# ADC_Board.net
KiCad netlist of a schematic drawn in EAGLE
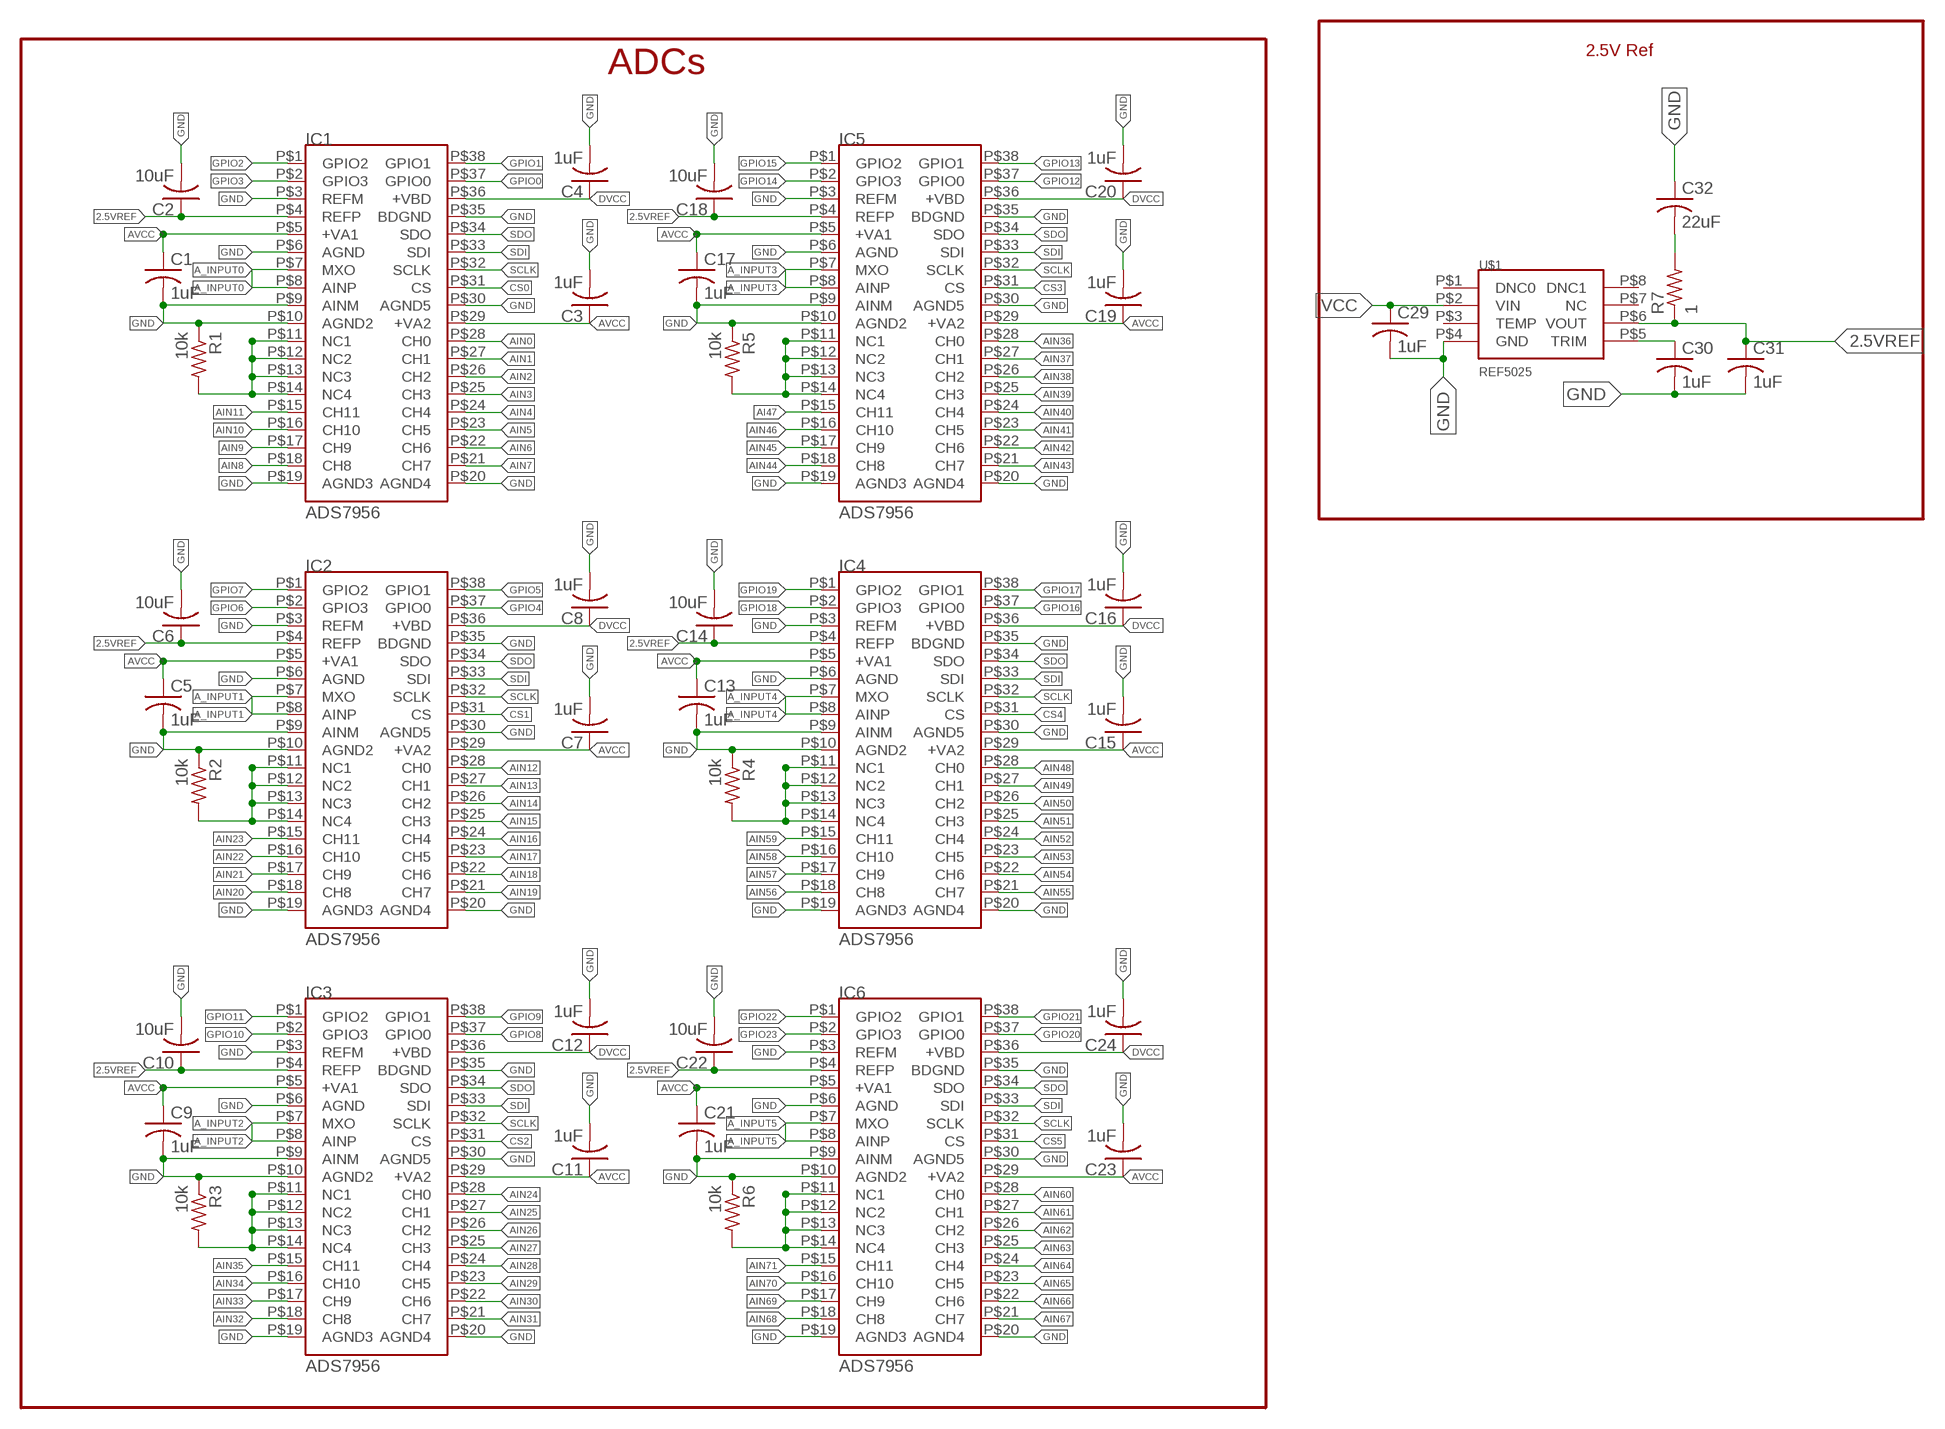
[diagram p0: schematic, sheet 1]

(export (version "E")
  (design (tool "Eeschema 10.0.6"))
  (components
    (comp (ref "C1")
      (value "1uF")
      (footprint "eagle-import:C0603")
      (libsource (lib "eagle-import") (part "C-USC0603"))
    )
    (comp (ref "C2")
      (value "10uF")
      (footprint "eagle-import:C0603")
      (libsource (lib "eagle-import") (part "C-USC0603"))
    )
    (comp (ref "C3")
      (value "1uF")
      (footprint "eagle-import:C0603")
      (libsource (lib "eagle-import") (part "C-USC0603"))
    )
    (comp (ref "C4")
      (value "1uF")
      (footprint "eagle-import:C0603")
      (libsource (lib "eagle-import") (part "C-USC0603"))
    )
    (comp (ref "C5")
      (value "1uF")
      (footprint "eagle-import:C0603")
      (libsource (lib "eagle-import") (part "C-USC0603"))
    )
    (comp (ref "C6")
      (value "10uF")
      (footprint "eagle-import:C0603")
      (libsource (lib "eagle-import") (part "C-USC0603"))
    )
    (comp (ref "C7")
      (value "1uF")
      (footprint "eagle-import:C0603")
      (libsource (lib "eagle-import") (part "C-USC0603"))
    )
    (comp (ref "C8")
      (value "1uF")
      (footprint "eagle-import:C0603")
      (libsource (lib "eagle-import") (part "C-USC0603"))
    )
    (comp (ref "C9")
      (value "1uF")
      (footprint "eagle-import:C0603")
      (libsource (lib "eagle-import") (part "C-USC0603"))
    )
    (comp (ref "C10")
      (value "10uF")
      (footprint "eagle-import:C0603")
      (libsource (lib "eagle-import") (part "C-USC0603"))
    )
    (comp (ref "C11")
      (value "1uF")
      (footprint "eagle-import:C0603")
      (libsource (lib "eagle-import") (part "C-USC0603"))
    )
    (comp (ref "C12")
      (value "1uF")
      (footprint "eagle-import:C0603")
      (libsource (lib "eagle-import") (part "C-USC0603"))
    )
    (comp (ref "C13")
      (value "1uF")
      (footprint "eagle-import:C0603")
      (libsource (lib "eagle-import") (part "C-USC0603"))
    )
    (comp (ref "C14")
      (value "10uF")
      (footprint "eagle-import:C0603")
      (libsource (lib "eagle-import") (part "C-USC0603"))
    )
    (comp (ref "C15")
      (value "1uF")
      (footprint "eagle-import:C0603")
      (libsource (lib "eagle-import") (part "C-USC0603"))
    )
    (comp (ref "C16")
      (value "1uF")
      (footprint "eagle-import:C0603")
      (libsource (lib "eagle-import") (part "C-USC0603"))
    )
    (comp (ref "C17")
      (value "1uF")
      (footprint "eagle-import:C0603")
      (libsource (lib "eagle-import") (part "C-USC0603"))
    )
    (comp (ref "C18")
      (value "10uF")
      (footprint "eagle-import:C0603")
      (libsource (lib "eagle-import") (part "C-USC0603"))
    )
    (comp (ref "C19")
      (value "1uF")
      (footprint "eagle-import:C0603")
      (libsource (lib "eagle-import") (part "C-USC0603"))
    )
    (comp (ref "C20")
      (value "1uF")
      (footprint "eagle-import:C0603")
      (libsource (lib "eagle-import") (part "C-USC0603"))
    )
    (comp (ref "C21")
      (value "1uF")
      (footprint "eagle-import:C0603")
      (libsource (lib "eagle-import") (part "C-USC0603"))
    )
    (comp (ref "C22")
      (value "10uF")
      (footprint "eagle-import:C0603")
      (libsource (lib "eagle-import") (part "C-USC0603"))
    )
    (comp (ref "C23")
      (value "1uF")
      (footprint "eagle-import:C0603")
      (libsource (lib "eagle-import") (part "C-USC0603"))
    )
    (comp (ref "C24")
      (value "1uF")
      (footprint "eagle-import:C0603")
      (libsource (lib "eagle-import") (part "C-USC0603"))
    )
    (comp (ref "C29")
      (value "1uF")
      (footprint "eagle-import:C0603")
      (libsource (lib "eagle-import") (part "C-USC0603"))
    )
    (comp (ref "C30")
      (value "1uF")
      (footprint "eagle-import:C0603")
      (libsource (lib "eagle-import") (part "C-USC0603"))
    )
    (comp (ref "C31")
      (value "1uF")
      (footprint "eagle-import:C0603")
      (libsource (lib "eagle-import") (part "C-USC0603"))
    )
    (comp (ref "C32")
      (value "22uF")
      (footprint "eagle-import:C0603")
      (libsource (lib "eagle-import") (part "C-USC0603"))
    )
    (comp (ref "IC1")
      (value "ADS7956")
      (footprint "eagle-import:TSSOP-38")
      (libsource (lib "eagle-import") (part "ADS7956"))
    )
    (comp (ref "IC2")
      (value "ADS7956")
      (footprint "eagle-import:TSSOP-38")
      (libsource (lib "eagle-import") (part "ADS7956"))
    )
    (comp (ref "IC3")
      (value "ADS7956")
      (footprint "eagle-import:TSSOP-38")
      (libsource (lib "eagle-import") (part "ADS7956"))
    )
    (comp (ref "IC4")
      (value "ADS7956")
      (footprint "eagle-import:TSSOP-38")
      (libsource (lib "eagle-import") (part "ADS7956"))
    )
    (comp (ref "IC5")
      (value "ADS7956")
      (footprint "eagle-import:TSSOP-38")
      (libsource (lib "eagle-import") (part "ADS7956"))
    )
    (comp (ref "IC6")
      (value "ADS7956")
      (footprint "eagle-import:TSSOP-38")
      (libsource (lib "eagle-import") (part "ADS7956"))
    )
    (comp (ref "R1")
      (value "10k")
      (footprint "eagle-import:R0603")
      (libsource (lib "eagle-import") (part "resistor_R-US_R0603"))
    )
    (comp (ref "R2")
      (value "10k")
      (footprint "eagle-import:R0603")
      (libsource (lib "eagle-import") (part "resistor_R-US_R0603"))
    )
    (comp (ref "R3")
      (value "10k")
      (footprint "eagle-import:R0603")
      (libsource (lib "eagle-import") (part "resistor_R-US_R0603"))
    )
    (comp (ref "R4")
      (value "10k")
      (footprint "eagle-import:R0603")
      (libsource (lib "eagle-import") (part "resistor_R-US_R0603"))
    )
    (comp (ref "R5")
      (value "10k")
      (footprint "eagle-import:R0603")
      (libsource (lib "eagle-import") (part "resistor_R-US_R0603"))
    )
    (comp (ref "R6")
      (value "10k")
      (footprint "eagle-import:R0603")
      (libsource (lib "eagle-import") (part "resistor_R-US_R0603"))
    )
    (comp (ref "R7")
      (value "1")
      (footprint "eagle-import:M0805")
      (libsource (lib "eagle-import") (part "R-US_M0805"))
    )
    (comp (ref "U$1")
      (value "REF5025")
      (footprint "eagle-import:TSSOP-8(TI)")
      (libsource (lib "eagle-import") (part "REF5025"))
    )
  )
  (nets
    (net (code "1") (name "2.5VREF") (class "Default")
      (node (ref "C10") (pin "1") (pinfunction "1_1") (pintype "passive"))
      (node (ref "C14") (pin "1") (pinfunction "1_1") (pintype "passive"))
      (node (ref "C18") (pin "1") (pinfunction "1_1") (pintype "passive"))
      (node (ref "C2") (pin "1") (pinfunction "1_1") (pintype "passive"))
      (node (ref "C22") (pin "1") (pinfunction "1_1") (pintype "passive"))
      (node (ref "C31") (pin "1") (pinfunction "1_1") (pintype "passive"))
      (node (ref "C6") (pin "1") (pinfunction "1_1") (pintype "passive"))
      (node (ref "IC1") (pin "P$4") (pinfunction "REFP_P$4") (pintype "bidirectional"))
      (node (ref "IC2") (pin "P$4") (pinfunction "REFP_P$4") (pintype "bidirectional"))
      (node (ref "IC3") (pin "P$4") (pinfunction "REFP_P$4") (pintype "bidirectional"))
      (node (ref "IC4") (pin "P$4") (pinfunction "REFP_P$4") (pintype "bidirectional"))
      (node (ref "IC5") (pin "P$4") (pinfunction "REFP_P$4") (pintype "bidirectional"))
      (node (ref "IC6") (pin "P$4") (pinfunction "REFP_P$4") (pintype "bidirectional"))
      (node (ref "R7") (pin "1") (pinfunction "1_1") (pintype "passive"))
      (node (ref "U$1") (pin "P$6") (pinfunction "VOUT_P$6") (pintype "bidirectional"))
    )
    (net (code "2") (name "AI47") (class "Default")
      (node (ref "IC5") (pin "P$15") (pinfunction "CH11_P$15") (pintype "bidirectional"))
    )
    (net (code "3") (name "AIN0") (class "Default")
      (node (ref "IC1") (pin "P$28") (pinfunction "CH0_P$28") (pintype "bidirectional"))
    )
    (net (code "4") (name "AIN1") (class "Default")
      (node (ref "IC1") (pin "P$27") (pinfunction "CH1_P$27") (pintype "bidirectional"))
    )
    (net (code "5") (name "AIN2") (class "Default")
      (node (ref "IC1") (pin "P$26") (pinfunction "CH2_P$26") (pintype "bidirectional"))
    )
    (net (code "6") (name "AIN3") (class "Default")
      (node (ref "IC1") (pin "P$25") (pinfunction "CH3_P$25") (pintype "bidirectional"))
    )
    (net (code "7") (name "AIN4") (class "Default")
      (node (ref "IC1") (pin "P$24") (pinfunction "CH4_P$24") (pintype "bidirectional"))
    )
    (net (code "8") (name "AIN5") (class "Default")
      (node (ref "IC1") (pin "P$23") (pinfunction "CH5_P$23") (pintype "bidirectional"))
    )
    (net (code "9") (name "AIN6") (class "Default")
      (node (ref "IC1") (pin "P$22") (pinfunction "CH6_P$22") (pintype "bidirectional"))
    )
    (net (code "10") (name "AIN7") (class "Default")
      (node (ref "IC1") (pin "P$21") (pinfunction "CH7_P$21") (pintype "bidirectional"))
    )
    (net (code "11") (name "AIN8") (class "Default")
      (node (ref "IC1") (pin "P$18") (pinfunction "CH8_P$18") (pintype "bidirectional"))
    )
    (net (code "12") (name "AIN9") (class "Default")
      (node (ref "IC1") (pin "P$17") (pinfunction "CH9_P$17") (pintype "bidirectional"))
    )
    (net (code "13") (name "AIN10") (class "Default")
      (node (ref "IC1") (pin "P$16") (pinfunction "CH10_P$16") (pintype "bidirectional"))
    )
    (net (code "14") (name "AIN11") (class "Default")
      (node (ref "IC1") (pin "P$15") (pinfunction "CH11_P$15") (pintype "bidirectional"))
    )
    (net (code "15") (name "AIN12") (class "Default")
      (node (ref "IC2") (pin "P$28") (pinfunction "CH0_P$28") (pintype "bidirectional"))
    )
    (net (code "16") (name "AIN13") (class "Default")
      (node (ref "IC2") (pin "P$27") (pinfunction "CH1_P$27") (pintype "bidirectional"))
    )
    (net (code "17") (name "AIN14") (class "Default")
      (node (ref "IC2") (pin "P$26") (pinfunction "CH2_P$26") (pintype "bidirectional"))
    )
    (net (code "18") (name "AIN15") (class "Default")
      (node (ref "IC2") (pin "P$25") (pinfunction "CH3_P$25") (pintype "bidirectional"))
    )
    (net (code "19") (name "AIN16") (class "Default")
      (node (ref "IC2") (pin "P$24") (pinfunction "CH4_P$24") (pintype "bidirectional"))
    )
    (net (code "20") (name "AIN17") (class "Default")
      (node (ref "IC2") (pin "P$23") (pinfunction "CH5_P$23") (pintype "bidirectional"))
    )
    (net (code "21") (name "AIN18") (class "Default")
      (node (ref "IC2") (pin "P$22") (pinfunction "CH6_P$22") (pintype "bidirectional"))
    )
    (net (code "22") (name "AIN19") (class "Default")
      (node (ref "IC2") (pin "P$21") (pinfunction "CH7_P$21") (pintype "bidirectional"))
    )
    (net (code "23") (name "AIN20") (class "Default")
      (node (ref "IC2") (pin "P$18") (pinfunction "CH8_P$18") (pintype "bidirectional"))
    )
    (net (code "24") (name "AIN21") (class "Default")
      (node (ref "IC2") (pin "P$17") (pinfunction "CH9_P$17") (pintype "bidirectional"))
    )
    (net (code "25") (name "AIN22") (class "Default")
      (node (ref "IC2") (pin "P$16") (pinfunction "CH10_P$16") (pintype "bidirectional"))
    )
    (net (code "26") (name "AIN23") (class "Default")
      (node (ref "IC2") (pin "P$15") (pinfunction "CH11_P$15") (pintype "bidirectional"))
    )
    (net (code "27") (name "AIN24") (class "Default")
      (node (ref "IC3") (pin "P$28") (pinfunction "CH0_P$28") (pintype "bidirectional"))
    )
    (net (code "28") (name "AIN25") (class "Default")
      (node (ref "IC3") (pin "P$27") (pinfunction "CH1_P$27") (pintype "bidirectional"))
    )
    (net (code "29") (name "AIN26") (class "Default")
      (node (ref "IC3") (pin "P$26") (pinfunction "CH2_P$26") (pintype "bidirectional"))
    )
    (net (code "30") (name "AIN27") (class "Default")
      (node (ref "IC3") (pin "P$25") (pinfunction "CH3_P$25") (pintype "bidirectional"))
    )
    (net (code "31") (name "AIN28") (class "Default")
      (node (ref "IC3") (pin "P$24") (pinfunction "CH4_P$24") (pintype "bidirectional"))
    )
    (net (code "32") (name "AIN29") (class "Default")
      (node (ref "IC3") (pin "P$23") (pinfunction "CH5_P$23") (pintype "bidirectional"))
    )
    (net (code "33") (name "AIN30") (class "Default")
      (node (ref "IC3") (pin "P$22") (pinfunction "CH6_P$22") (pintype "bidirectional"))
    )
    (net (code "34") (name "AIN31") (class "Default")
      (node (ref "IC3") (pin "P$21") (pinfunction "CH7_P$21") (pintype "bidirectional"))
    )
    (net (code "35") (name "AIN32") (class "Default")
      (node (ref "IC3") (pin "P$18") (pinfunction "CH8_P$18") (pintype "bidirectional"))
    )
    (net (code "36") (name "AIN33") (class "Default")
      (node (ref "IC3") (pin "P$17") (pinfunction "CH9_P$17") (pintype "bidirectional"))
    )
    (net (code "37") (name "AIN34") (class "Default")
      (node (ref "IC3") (pin "P$16") (pinfunction "CH10_P$16") (pintype "bidirectional"))
    )
    (net (code "38") (name "AIN35") (class "Default")
      (node (ref "IC3") (pin "P$15") (pinfunction "CH11_P$15") (pintype "bidirectional"))
    )
    (net (code "39") (name "AIN36") (class "Default")
      (node (ref "IC5") (pin "P$28") (pinfunction "CH0_P$28") (pintype "bidirectional"))
    )
    (net (code "40") (name "AIN37") (class "Default")
      (node (ref "IC5") (pin "P$27") (pinfunction "CH1_P$27") (pintype "bidirectional"))
    )
    (net (code "41") (name "AIN38") (class "Default")
      (node (ref "IC5") (pin "P$26") (pinfunction "CH2_P$26") (pintype "bidirectional"))
    )
    (net (code "42") (name "AIN39") (class "Default")
      (node (ref "IC5") (pin "P$25") (pinfunction "CH3_P$25") (pintype "bidirectional"))
    )
    (net (code "43") (name "AIN40") (class "Default")
      (node (ref "IC5") (pin "P$24") (pinfunction "CH4_P$24") (pintype "bidirectional"))
    )
    (net (code "44") (name "AIN41") (class "Default")
      (node (ref "IC5") (pin "P$23") (pinfunction "CH5_P$23") (pintype "bidirectional"))
    )
    (net (code "45") (name "AIN42") (class "Default")
      (node (ref "IC5") (pin "P$22") (pinfunction "CH6_P$22") (pintype "bidirectional"))
    )
    (net (code "46") (name "AIN43") (class "Default")
      (node (ref "IC5") (pin "P$21") (pinfunction "CH7_P$21") (pintype "bidirectional"))
    )
    (net (code "47") (name "AIN44") (class "Default")
      (node (ref "IC5") (pin "P$18") (pinfunction "CH8_P$18") (pintype "bidirectional"))
    )
    (net (code "48") (name "AIN45") (class "Default")
      (node (ref "IC5") (pin "P$17") (pinfunction "CH9_P$17") (pintype "bidirectional"))
    )
    (net (code "49") (name "AIN46") (class "Default")
      (node (ref "IC5") (pin "P$16") (pinfunction "CH10_P$16") (pintype "bidirectional"))
    )
    (net (code "50") (name "AIN48") (class "Default")
      (node (ref "IC4") (pin "P$28") (pinfunction "CH0_P$28") (pintype "bidirectional"))
    )
    (net (code "51") (name "AIN49") (class "Default")
      (node (ref "IC4") (pin "P$27") (pinfunction "CH1_P$27") (pintype "bidirectional"))
    )
    (net (code "52") (name "AIN50") (class "Default")
      (node (ref "IC4") (pin "P$26") (pinfunction "CH2_P$26") (pintype "bidirectional"))
    )
    (net (code "53") (name "AIN51") (class "Default")
      (node (ref "IC4") (pin "P$25") (pinfunction "CH3_P$25") (pintype "bidirectional"))
    )
    (net (code "54") (name "AIN52") (class "Default")
      (node (ref "IC4") (pin "P$24") (pinfunction "CH4_P$24") (pintype "bidirectional"))
    )
    (net (code "55") (name "AIN53") (class "Default")
      (node (ref "IC4") (pin "P$23") (pinfunction "CH5_P$23") (pintype "bidirectional"))
    )
    (net (code "56") (name "AIN54") (class "Default")
      (node (ref "IC4") (pin "P$22") (pinfunction "CH6_P$22") (pintype "bidirectional"))
    )
    (net (code "57") (name "AIN55") (class "Default")
      (node (ref "IC4") (pin "P$21") (pinfunction "CH7_P$21") (pintype "bidirectional"))
    )
    (net (code "58") (name "AIN56") (class "Default")
      (node (ref "IC4") (pin "P$18") (pinfunction "CH8_P$18") (pintype "bidirectional"))
    )
    (net (code "59") (name "AIN57") (class "Default")
      (node (ref "IC4") (pin "P$17") (pinfunction "CH9_P$17") (pintype "bidirectional"))
    )
    (net (code "60") (name "AIN58") (class "Default")
      (node (ref "IC4") (pin "P$16") (pinfunction "CH10_P$16") (pintype "bidirectional"))
    )
    (net (code "61") (name "AIN59") (class "Default")
      (node (ref "IC4") (pin "P$15") (pinfunction "CH11_P$15") (pintype "bidirectional"))
    )
    (net (code "62") (name "AIN60") (class "Default")
      (node (ref "IC6") (pin "P$28") (pinfunction "CH0_P$28") (pintype "bidirectional"))
    )
    (net (code "63") (name "AIN61") (class "Default")
      (node (ref "IC6") (pin "P$27") (pinfunction "CH1_P$27") (pintype "bidirectional"))
    )
    (net (code "64") (name "AIN62") (class "Default")
      (node (ref "IC6") (pin "P$26") (pinfunction "CH2_P$26") (pintype "bidirectional"))
    )
    (net (code "65") (name "AIN63") (class "Default")
      (node (ref "IC6") (pin "P$25") (pinfunction "CH3_P$25") (pintype "bidirectional"))
    )
    (net (code "66") (name "AIN64") (class "Default")
      (node (ref "IC6") (pin "P$24") (pinfunction "CH4_P$24") (pintype "bidirectional"))
    )
    (net (code "67") (name "AIN65") (class "Default")
      (node (ref "IC6") (pin "P$23") (pinfunction "CH5_P$23") (pintype "bidirectional"))
    )
    (net (code "68") (name "AIN66") (class "Default")
      (node (ref "IC6") (pin "P$22") (pinfunction "CH6_P$22") (pintype "bidirectional"))
    )
    (net (code "69") (name "AIN67") (class "Default")
      (node (ref "IC6") (pin "P$21") (pinfunction "CH7_P$21") (pintype "bidirectional"))
    )
    (net (code "70") (name "AIN68") (class "Default")
      (node (ref "IC6") (pin "P$18") (pinfunction "CH8_P$18") (pintype "bidirectional"))
    )
    (net (code "71") (name "AIN69") (class "Default")
      (node (ref "IC6") (pin "P$17") (pinfunction "CH9_P$17") (pintype "bidirectional"))
    )
    (net (code "72") (name "AIN70") (class "Default")
      (node (ref "IC6") (pin "P$16") (pinfunction "CH10_P$16") (pintype "bidirectional"))
    )
    (net (code "73") (name "AIN71") (class "Default")
      (node (ref "IC6") (pin "P$15") (pinfunction "CH11_P$15") (pintype "bidirectional"))
    )
    (net (code "74") (name "AVCC") (class "Default")
      (node (ref "C1") (pin "1") (pinfunction "1_1") (pintype "passive"))
      (node (ref "C11") (pin "1") (pinfunction "1_1") (pintype "passive"))
      (node (ref "C13") (pin "1") (pinfunction "1_1") (pintype "passive"))
      (node (ref "C15") (pin "1") (pinfunction "1_1") (pintype "passive"))
      (node (ref "C17") (pin "1") (pinfunction "1_1") (pintype "passive"))
      (node (ref "C19") (pin "1") (pinfunction "1_1") (pintype "passive"))
      (node (ref "C21") (pin "1") (pinfunction "1_1") (pintype "passive"))
      (node (ref "C23") (pin "1") (pinfunction "1_1") (pintype "passive"))
      (node (ref "C3") (pin "1") (pinfunction "1_1") (pintype "passive"))
      (node (ref "C5") (pin "1") (pinfunction "1_1") (pintype "passive"))
      (node (ref "C7") (pin "1") (pinfunction "1_1") (pintype "passive"))
      (node (ref "C9") (pin "1") (pinfunction "1_1") (pintype "passive"))
      (node (ref "IC1") (pin "P$29") (pinfunction "+VA2_P$29") (pintype "bidirectional"))
      (node (ref "IC1") (pin "P$5") (pinfunction "+VA1_P$5") (pintype "bidirectional"))
      (node (ref "IC2") (pin "P$29") (pinfunction "+VA2_P$29") (pintype "bidirectional"))
      (node (ref "IC2") (pin "P$5") (pinfunction "+VA1_P$5") (pintype "bidirectional"))
      (node (ref "IC3") (pin "P$29") (pinfunction "+VA2_P$29") (pintype "bidirectional"))
      (node (ref "IC3") (pin "P$5") (pinfunction "+VA1_P$5") (pintype "bidirectional"))
      (node (ref "IC4") (pin "P$29") (pinfunction "+VA2_P$29") (pintype "bidirectional"))
      (node (ref "IC4") (pin "P$5") (pinfunction "+VA1_P$5") (pintype "bidirectional"))
      (node (ref "IC5") (pin "P$29") (pinfunction "+VA2_P$29") (pintype "bidirectional"))
      (node (ref "IC5") (pin "P$5") (pinfunction "+VA1_P$5") (pintype "bidirectional"))
      (node (ref "IC6") (pin "P$29") (pinfunction "+VA2_P$29") (pintype "bidirectional"))
      (node (ref "IC6") (pin "P$5") (pinfunction "+VA1_P$5") (pintype "bidirectional"))
    )
    (net (code "75") (name "A_INPUT0") (class "Default")
      (node (ref "IC1") (pin "P$7") (pinfunction "MXO_P$7") (pintype "bidirectional"))
      (node (ref "IC1") (pin "P$8") (pinfunction "AINP_P$8") (pintype "bidirectional"))
    )
    (net (code "76") (name "A_INPUT1") (class "Default")
      (node (ref "IC2") (pin "P$7") (pinfunction "MXO_P$7") (pintype "bidirectional"))
      (node (ref "IC2") (pin "P$8") (pinfunction "AINP_P$8") (pintype "bidirectional"))
    )
    (net (code "77") (name "A_INPUT2") (class "Default")
      (node (ref "IC3") (pin "P$7") (pinfunction "MXO_P$7") (pintype "bidirectional"))
      (node (ref "IC3") (pin "P$8") (pinfunction "AINP_P$8") (pintype "bidirectional"))
    )
    (net (code "78") (name "A_INPUT3") (class "Default")
      (node (ref "IC5") (pin "P$7") (pinfunction "MXO_P$7") (pintype "bidirectional"))
      (node (ref "IC5") (pin "P$8") (pinfunction "AINP_P$8") (pintype "bidirectional"))
    )
    (net (code "79") (name "A_INPUT4") (class "Default")
      (node (ref "IC4") (pin "P$7") (pinfunction "MXO_P$7") (pintype "bidirectional"))
      (node (ref "IC4") (pin "P$8") (pinfunction "AINP_P$8") (pintype "bidirectional"))
    )
    (net (code "80") (name "A_INPUT5") (class "Default")
      (node (ref "IC6") (pin "P$7") (pinfunction "MXO_P$7") (pintype "bidirectional"))
      (node (ref "IC6") (pin "P$8") (pinfunction "AINP_P$8") (pintype "bidirectional"))
    )
    (net (code "81") (name "CS0") (class "Default")
      (node (ref "IC1") (pin "P$31") (pinfunction "CS_P$31") (pintype "bidirectional"))
    )
    (net (code "82") (name "CS1") (class "Default")
      (node (ref "IC2") (pin "P$31") (pinfunction "CS_P$31") (pintype "bidirectional"))
    )
    (net (code "83") (name "CS2") (class "Default")
      (node (ref "IC3") (pin "P$31") (pinfunction "CS_P$31") (pintype "bidirectional"))
    )
    (net (code "84") (name "CS3") (class "Default")
      (node (ref "IC5") (pin "P$31") (pinfunction "CS_P$31") (pintype "bidirectional"))
    )
    (net (code "85") (name "CS4") (class "Default")
      (node (ref "IC4") (pin "P$31") (pinfunction "CS_P$31") (pintype "bidirectional"))
    )
    (net (code "86") (name "CS5") (class "Default")
      (node (ref "IC6") (pin "P$31") (pinfunction "CS_P$31") (pintype "bidirectional"))
    )
    (net (code "87") (name "DVCC") (class "Default")
      (node (ref "C12") (pin "1") (pinfunction "1_1") (pintype "passive"))
      (node (ref "C16") (pin "1") (pinfunction "1_1") (pintype "passive"))
      (node (ref "C20") (pin "1") (pinfunction "1_1") (pintype "passive"))
      (node (ref "C24") (pin "1") (pinfunction "1_1") (pintype "passive"))
      (node (ref "C4") (pin "1") (pinfunction "1_1") (pintype "passive"))
      (node (ref "C8") (pin "1") (pinfunction "1_1") (pintype "passive"))
      (node (ref "IC1") (pin "P$36") (pinfunction "+VBD_P$36") (pintype "bidirectional"))
      (node (ref "IC2") (pin "P$36") (pinfunction "+VBD_P$36") (pintype "bidirectional"))
      (node (ref "IC3") (pin "P$36") (pinfunction "+VBD_P$36") (pintype "bidirectional"))
      (node (ref "IC4") (pin "P$36") (pinfunction "+VBD_P$36") (pintype "bidirectional"))
      (node (ref "IC5") (pin "P$36") (pinfunction "+VBD_P$36") (pintype "bidirectional"))
      (node (ref "IC6") (pin "P$36") (pinfunction "+VBD_P$36") (pintype "bidirectional"))
    )
    (net (code "88") (name "GND") (class "Default")
      (node (ref "C1") (pin "2") (pinfunction "2_2") (pintype "passive"))
      (node (ref "C10") (pin "2") (pinfunction "2_2") (pintype "passive"))
      (node (ref "C11") (pin "2") (pinfunction "2_2") (pintype "passive"))
      (node (ref "C12") (pin "2") (pinfunction "2_2") (pintype "passive"))
      (node (ref "C13") (pin "2") (pinfunction "2_2") (pintype "passive"))
      (node (ref "C14") (pin "2") (pinfunction "2_2") (pintype "passive"))
      (node (ref "C15") (pin "2") (pinfunction "2_2") (pintype "passive"))
      (node (ref "C16") (pin "2") (pinfunction "2_2") (pintype "passive"))
      (node (ref "C17") (pin "2") (pinfunction "2_2") (pintype "passive"))
      (node (ref "C18") (pin "2") (pinfunction "2_2") (pintype "passive"))
      (node (ref "C19") (pin "2") (pinfunction "2_2") (pintype "passive"))
      (node (ref "C2") (pin "2") (pinfunction "2_2") (pintype "passive"))
      (node (ref "C20") (pin "2") (pinfunction "2_2") (pintype "passive"))
      (node (ref "C21") (pin "2") (pinfunction "2_2") (pintype "passive"))
      (node (ref "C22") (pin "2") (pinfunction "2_2") (pintype "passive"))
      (node (ref "C23") (pin "2") (pinfunction "2_2") (pintype "passive"))
      (node (ref "C24") (pin "2") (pinfunction "2_2") (pintype "passive"))
      (node (ref "C29") (pin "2") (pinfunction "2_2") (pintype "passive"))
      (node (ref "C3") (pin "2") (pinfunction "2_2") (pintype "passive"))
      (node (ref "C30") (pin "2") (pinfunction "2_2") (pintype "passive"))
      (node (ref "C31") (pin "2") (pinfunction "2_2") (pintype "passive"))
      (node (ref "C32") (pin "1") (pinfunction "1_1") (pintype "passive"))
      (node (ref "C4") (pin "2") (pinfunction "2_2") (pintype "passive"))
      (node (ref "C5") (pin "2") (pinfunction "2_2") (pintype "passive"))
      (node (ref "C6") (pin "2") (pinfunction "2_2") (pintype "passive"))
      (node (ref "C7") (pin "2") (pinfunction "2_2") (pintype "passive"))
      (node (ref "C8") (pin "2") (pinfunction "2_2") (pintype "passive"))
      (node (ref "C9") (pin "2") (pinfunction "2_2") (pintype "passive"))
      (node (ref "IC1") (pin "P$10") (pinfunction "AGND2_P$10") (pintype "bidirectional"))
      (node (ref "IC1") (pin "P$19") (pinfunction "AGND3_P$19") (pintype "bidirectional"))
      (node (ref "IC1") (pin "P$20") (pinfunction "AGND4_P$20") (pintype "bidirectional"))
      (node (ref "IC1") (pin "P$3") (pinfunction "REFM_P$3") (pintype "bidirectional"))
      (node (ref "IC1") (pin "P$30") (pinfunction "AGND5_P$30") (pintype "bidirectional"))
      (node (ref "IC1") (pin "P$35") (pinfunction "BDGND_P$35") (pintype "bidirectional"))
      (node (ref "IC1") (pin "P$6") (pinfunction "AGND_P$6") (pintype "bidirectional"))
      (node (ref "IC1") (pin "P$9") (pinfunction "AINM_P$9") (pintype "bidirectional"))
      (node (ref "IC2") (pin "P$10") (pinfunction "AGND2_P$10") (pintype "bidirectional"))
      (node (ref "IC2") (pin "P$19") (pinfunction "AGND3_P$19") (pintype "bidirectional"))
      (node (ref "IC2") (pin "P$20") (pinfunction "AGND4_P$20") (pintype "bidirectional"))
      (node (ref "IC2") (pin "P$3") (pinfunction "REFM_P$3") (pintype "bidirectional"))
      (node (ref "IC2") (pin "P$30") (pinfunction "AGND5_P$30") (pintype "bidirectional"))
      (node (ref "IC2") (pin "P$35") (pinfunction "BDGND_P$35") (pintype "bidirectional"))
      (node (ref "IC2") (pin "P$6") (pinfunction "AGND_P$6") (pintype "bidirectional"))
      (node (ref "IC2") (pin "P$9") (pinfunction "AINM_P$9") (pintype "bidirectional"))
      (node (ref "IC3") (pin "P$10") (pinfunction "AGND2_P$10") (pintype "bidirectional"))
      (node (ref "IC3") (pin "P$19") (pinfunction "AGND3_P$19") (pintype "bidirectional"))
      (node (ref "IC3") (pin "P$20") (pinfunction "AGND4_P$20") (pintype "bidirectional"))
      (node (ref "IC3") (pin "P$3") (pinfunction "REFM_P$3") (pintype "bidirectional"))
      (node (ref "IC3") (pin "P$30") (pinfunction "AGND5_P$30") (pintype "bidirectional"))
      (node (ref "IC3") (pin "P$35") (pinfunction "BDGND_P$35") (pintype "bidirectional"))
      (node (ref "IC3") (pin "P$6") (pinfunction "AGND_P$6") (pintype "bidirectional"))
      (node (ref "IC3") (pin "P$9") (pinfunction "AINM_P$9") (pintype "bidirectional"))
      (node (ref "IC4") (pin "P$10") (pinfunction "AGND2_P$10") (pintype "bidirectional"))
      (node (ref "IC4") (pin "P$19") (pinfunction "AGND3_P$19") (pintype "bidirectional"))
      (node (ref "IC4") (pin "P$20") (pinfunction "AGND4_P$20") (pintype "bidirectional"))
      (node (ref "IC4") (pin "P$3") (pinfunction "REFM_P$3") (pintype "bidirectional"))
      (node (ref "IC4") (pin "P$30") (pinfunction "AGND5_P$30") (pintype "bidirectional"))
      (node (ref "IC4") (pin "P$35") (pinfunction "BDGND_P$35") (pintype "bidirectional"))
      (node (ref "IC4") (pin "P$6") (pinfunction "AGND_P$6") (pintype "bidirectional"))
      (node (ref "IC4") (pin "P$9") (pinfunction "AINM_P$9") (pintype "bidirectional"))
      (node (ref "IC5") (pin "P$10") (pinfunction "AGND2_P$10") (pintype "bidirectional"))
      (node (ref "IC5") (pin "P$19") (pinfunction "AGND3_P$19") (pintype "bidirectional"))
      (node (ref "IC5") (pin "P$20") (pinfunction "AGND4_P$20") (pintype "bidirectional"))
      (node (ref "IC5") (pin "P$3") (pinfunction "REFM_P$3") (pintype "bidirectional"))
      (node (ref "IC5") (pin "P$30") (pinfunction "AGND5_P$30") (pintype "bidirectional"))
      (node (ref "IC5") (pin "P$35") (pinfunction "BDGND_P$35") (pintype "bidirectional"))
      (node (ref "IC5") (pin "P$6") (pinfunction "AGND_P$6") (pintype "bidirectional"))
      (node (ref "IC5") (pin "P$9") (pinfunction "AINM_P$9") (pintype "bidirectional"))
      (node (ref "IC6") (pin "P$10") (pinfunction "AGND2_P$10") (pintype "bidirectional"))
      (node (ref "IC6") (pin "P$19") (pinfunction "AGND3_P$19") (pintype "bidirectional"))
      (node (ref "IC6") (pin "P$20") (pinfunction "AGND4_P$20") (pintype "bidirectional"))
      (node (ref "IC6") (pin "P$3") (pinfunction "REFM_P$3") (pintype "bidirectional"))
      (node (ref "IC6") (pin "P$30") (pinfunction "AGND5_P$30") (pintype "bidirectional"))
      (node (ref "IC6") (pin "P$35") (pinfunction "BDGND_P$35") (pintype "bidirectional"))
      (node (ref "IC6") (pin "P$6") (pinfunction "AGND_P$6") (pintype "bidirectional"))
      (node (ref "IC6") (pin "P$9") (pinfunction "AINM_P$9") (pintype "bidirectional"))
      (node (ref "R1") (pin "1") (pinfunction "1_1") (pintype "passive"))
      (node (ref "R2") (pin "1") (pinfunction "1_1") (pintype "passive"))
      (node (ref "R3") (pin "1") (pinfunction "1_1") (pintype "passive"))
      (node (ref "R4") (pin "1") (pinfunction "1_1") (pintype "passive"))
      (node (ref "R5") (pin "1") (pinfunction "1_1") (pintype "passive"))
      (node (ref "R6") (pin "1") (pinfunction "1_1") (pintype "passive"))
      (node (ref "U$1") (pin "P$4") (pinfunction "GND_P$4") (pintype "bidirectional"))
    )
    (net (code "89") (name "GPIO0") (class "Default")
      (node (ref "IC1") (pin "P$37") (pinfunction "GPIO0_P$37") (pintype "bidirectional"))
    )
    (net (code "90") (name "GPIO1") (class "Default")
      (node (ref "IC1") (pin "P$38") (pinfunction "GPIO1_P$38") (pintype "bidirectional"))
    )
    (net (code "91") (name "GPIO2") (class "Default")
      (node (ref "IC1") (pin "P$1") (pinfunction "GPIO2_P$1") (pintype "bidirectional"))
    )
    (net (code "92") (name "GPIO3") (class "Default")
      (node (ref "IC1") (pin "P$2") (pinfunction "GPIO3_P$2") (pintype "bidirectional"))
    )
    (net (code "93") (name "GPIO4") (class "Default")
      (node (ref "IC2") (pin "P$37") (pinfunction "GPIO0_P$37") (pintype "bidirectional"))
    )
    (net (code "94") (name "GPIO5") (class "Default")
      (node (ref "IC2") (pin "P$38") (pinfunction "GPIO1_P$38") (pintype "bidirectional"))
    )
    (net (code "95") (name "GPIO6") (class "Default")
      (node (ref "IC2") (pin "P$2") (pinfunction "GPIO3_P$2") (pintype "bidirectional"))
    )
    (net (code "96") (name "GPIO7") (class "Default")
      (node (ref "IC2") (pin "P$1") (pinfunction "GPIO2_P$1") (pintype "bidirectional"))
    )
    (net (code "97") (name "GPIO8") (class "Default")
      (node (ref "IC3") (pin "P$37") (pinfunction "GPIO0_P$37") (pintype "bidirectional"))
    )
    (net (code "98") (name "GPIO9") (class "Default")
      (node (ref "IC3") (pin "P$38") (pinfunction "GPIO1_P$38") (pintype "bidirectional"))
    )
    (net (code "99") (name "GPIO10") (class "Default")
      (node (ref "IC3") (pin "P$2") (pinfunction "GPIO3_P$2") (pintype "bidirectional"))
    )
    (net (code "100") (name "GPIO11") (class "Default")
      (node (ref "IC3") (pin "P$1") (pinfunction "GPIO2_P$1") (pintype "bidirectional"))
    )
    (net (code "101") (name "GPIO12") (class "Default")
      (node (ref "IC5") (pin "P$37") (pinfunction "GPIO0_P$37") (pintype "bidirectional"))
    )
    (net (code "102") (name "GPIO13") (class "Default")
      (node (ref "IC5") (pin "P$38") (pinfunction "GPIO1_P$38") (pintype "bidirectional"))
    )
    (net (code "103") (name "GPIO14") (class "Default")
      (node (ref "IC5") (pin "P$2") (pinfunction "GPIO3_P$2") (pintype "bidirectional"))
    )
    (net (code "104") (name "GPIO15") (class "Default")
      (node (ref "IC5") (pin "P$1") (pinfunction "GPIO2_P$1") (pintype "bidirectional"))
    )
    (net (code "105") (name "GPIO16") (class "Default")
      (node (ref "IC4") (pin "P$37") (pinfunction "GPIO0_P$37") (pintype "bidirectional"))
    )
    (net (code "106") (name "GPIO17") (class "Default")
      (node (ref "IC4") (pin "P$38") (pinfunction "GPIO1_P$38") (pintype "bidirectional"))
    )
    (net (code "107") (name "GPIO18") (class "Default")
      (node (ref "IC4") (pin "P$2") (pinfunction "GPIO3_P$2") (pintype "bidirectional"))
    )
    (net (code "108") (name "GPIO19") (class "Default")
      (node (ref "IC4") (pin "P$1") (pinfunction "GPIO2_P$1") (pintype "bidirectional"))
    )
    (net (code "109") (name "GPIO20") (class "Default")
      (node (ref "IC6") (pin "P$37") (pinfunction "GPIO0_P$37") (pintype "bidirectional"))
    )
    (net (code "110") (name "GPIO21") (class "Default")
      (node (ref "IC6") (pin "P$38") (pinfunction "GPIO1_P$38") (pintype "bidirectional"))
    )
    (net (code "111") (name "GPIO22") (class "Default")
      (node (ref "IC6") (pin "P$1") (pinfunction "GPIO2_P$1") (pintype "bidirectional"))
    )
    (net (code "112") (name "GPIO23") (class "Default")
      (node (ref "IC6") (pin "P$2") (pinfunction "GPIO3_P$2") (pintype "bidirectional"))
    )
    (net (code "113") (name "Net-(C32-Pad2)") (class "Default")
      (node (ref "C32") (pin "2") (pinfunction "2_2") (pintype "passive"))
      (node (ref "R7") (pin "2") (pinfunction "2_2") (pintype "passive"))
    )
    (net (code "114") (name "Net-(IC1-NC1)") (class "Default")
      (node (ref "IC1") (pin "P$11") (pinfunction "NC1_P$11") (pintype "bidirectional"))
      (node (ref "IC1") (pin "P$12") (pinfunction "NC2_P$12") (pintype "bidirectional"))
      (node (ref "IC1") (pin "P$13") (pinfunction "NC3_P$13") (pintype "bidirectional"))
      (node (ref "IC1") (pin "P$14") (pinfunction "NC4_P$14") (pintype "bidirectional"))
      (node (ref "R1") (pin "2") (pinfunction "2_2") (pintype "passive"))
    )
    (net (code "115") (name "Net-(IC2-NC1)") (class "Default")
      (node (ref "IC2") (pin "P$11") (pinfunction "NC1_P$11") (pintype "bidirectional"))
      (node (ref "IC2") (pin "P$12") (pinfunction "NC2_P$12") (pintype "bidirectional"))
      (node (ref "IC2") (pin "P$13") (pinfunction "NC3_P$13") (pintype "bidirectional"))
      (node (ref "IC2") (pin "P$14") (pinfunction "NC4_P$14") (pintype "bidirectional"))
      (node (ref "R2") (pin "2") (pinfunction "2_2") (pintype "passive"))
    )
    (net (code "116") (name "Net-(IC3-NC1)") (class "Default")
      (node (ref "IC3") (pin "P$11") (pinfunction "NC1_P$11") (pintype "bidirectional"))
      (node (ref "IC3") (pin "P$12") (pinfunction "NC2_P$12") (pintype "bidirectional"))
      (node (ref "IC3") (pin "P$13") (pinfunction "NC3_P$13") (pintype "bidirectional"))
      (node (ref "IC3") (pin "P$14") (pinfunction "NC4_P$14") (pintype "bidirectional"))
      (node (ref "R3") (pin "2") (pinfunction "2_2") (pintype "passive"))
    )
    (net (code "117") (name "Net-(IC4-NC1)") (class "Default")
      (node (ref "IC4") (pin "P$11") (pinfunction "NC1_P$11") (pintype "bidirectional"))
      (node (ref "IC4") (pin "P$12") (pinfunction "NC2_P$12") (pintype "bidirectional"))
      (node (ref "IC4") (pin "P$13") (pinfunction "NC3_P$13") (pintype "bidirectional"))
      (node (ref "IC4") (pin "P$14") (pinfunction "NC4_P$14") (pintype "bidirectional"))
      (node (ref "R4") (pin "2") (pinfunction "2_2") (pintype "passive"))
    )
    (net (code "118") (name "Net-(IC5-NC1)") (class "Default")
      (node (ref "IC5") (pin "P$11") (pinfunction "NC1_P$11") (pintype "bidirectional"))
      (node (ref "IC5") (pin "P$12") (pinfunction "NC2_P$12") (pintype "bidirectional"))
      (node (ref "IC5") (pin "P$13") (pinfunction "NC3_P$13") (pintype "bidirectional"))
      (node (ref "IC5") (pin "P$14") (pinfunction "NC4_P$14") (pintype "bidirectional"))
      (node (ref "R5") (pin "2") (pinfunction "2_2") (pintype "passive"))
    )
    (net (code "119") (name "Net-(IC6-NC1)") (class "Default")
      (node (ref "IC6") (pin "P$11") (pinfunction "NC1_P$11") (pintype "bidirectional"))
      (node (ref "IC6") (pin "P$12") (pinfunction "NC2_P$12") (pintype "bidirectional"))
      (node (ref "IC6") (pin "P$13") (pinfunction "NC3_P$13") (pintype "bidirectional"))
      (node (ref "IC6") (pin "P$14") (pinfunction "NC4_P$14") (pintype "bidirectional"))
      (node (ref "R6") (pin "2") (pinfunction "2_2") (pintype "passive"))
    )
    (net (code "120") (name "Net-(U$1-TRIM)") (class "Default")
      (node (ref "C30") (pin "1") (pinfunction "1_1") (pintype "passive"))
      (node (ref "U$1") (pin "P$5") (pinfunction "TRIM_P$5") (pintype "bidirectional"))
    )
    (net (code "121") (name "SCLK") (class "Default")
      (node (ref "IC1") (pin "P$32") (pinfunction "SCLK_P$32") (pintype "bidirectional"))
      (node (ref "IC2") (pin "P$32") (pinfunction "SCLK_P$32") (pintype "bidirectional"))
      (node (ref "IC3") (pin "P$32") (pinfunction "SCLK_P$32") (pintype "bidirectional"))
      (node (ref "IC4") (pin "P$32") (pinfunction "SCLK_P$32") (pintype "bidirectional"))
      (node (ref "IC5") (pin "P$32") (pinfunction "SCLK_P$32") (pintype "bidirectional"))
      (node (ref "IC6") (pin "P$32") (pinfunction "SCLK_P$32") (pintype "bidirectional"))
    )
    (net (code "122") (name "SDI") (class "Default")
      (node (ref "IC1") (pin "P$33") (pinfunction "SDI_P$33") (pintype "bidirectional"))
      (node (ref "IC2") (pin "P$33") (pinfunction "SDI_P$33") (pintype "bidirectional"))
      (node (ref "IC3") (pin "P$33") (pinfunction "SDI_P$33") (pintype "bidirectional"))
      (node (ref "IC4") (pin "P$33") (pinfunction "SDI_P$33") (pintype "bidirectional"))
      (node (ref "IC5") (pin "P$33") (pinfunction "SDI_P$33") (pintype "bidirectional"))
      (node (ref "IC6") (pin "P$33") (pinfunction "SDI_P$33") (pintype "bidirectional"))
    )
    (net (code "123") (name "SDO") (class "Default")
      (node (ref "IC1") (pin "P$34") (pinfunction "SDO_P$34") (pintype "bidirectional"))
      (node (ref "IC2") (pin "P$34") (pinfunction "SDO_P$34") (pintype "bidirectional"))
      (node (ref "IC3") (pin "P$34") (pinfunction "SDO_P$34") (pintype "bidirectional"))
      (node (ref "IC4") (pin "P$34") (pinfunction "SDO_P$34") (pintype "bidirectional"))
      (node (ref "IC5") (pin "P$34") (pinfunction "SDO_P$34") (pintype "bidirectional"))
      (node (ref "IC6") (pin "P$34") (pinfunction "SDO_P$34") (pintype "bidirectional"))
    )
    (net (code "124") (name "VCC") (class "Default")
      (node (ref "C29") (pin "1") (pinfunction "1_1") (pintype "passive"))
      (node (ref "U$1") (pin "P$2") (pinfunction "VIN_P$2") (pintype "bidirectional"))
    )
    (net (code "125") (name "unconnected-(U$1-DNC0-PadP$1)") (class "Default")
      (node (ref "U$1") (pin "P$1") (pinfunction "DNC0_P$1") (pintype "bidirectional"))
    )
    (net (code "126") (name "unconnected-(U$1-DNC1-PadP$8)") (class "Default")
      (node (ref "U$1") (pin "P$8") (pinfunction "DNC1_P$8") (pintype "bidirectional"))
    )
    (net (code "127") (name "unconnected-(U$1-NC-PadP$7)") (class "Default")
      (node (ref "U$1") (pin "P$7") (pinfunction "NC_P$7") (pintype "bidirectional"))
    )
    (net (code "128") (name "unconnected-(U$1-TEMP-PadP$3)") (class "Default")
      (node (ref "U$1") (pin "P$3") (pinfunction "TEMP_P$3") (pintype "bidirectional"))
    )
  )
)
